# PowerSupply.net
KiCad netlist of a schematic drawn in Altium Designer
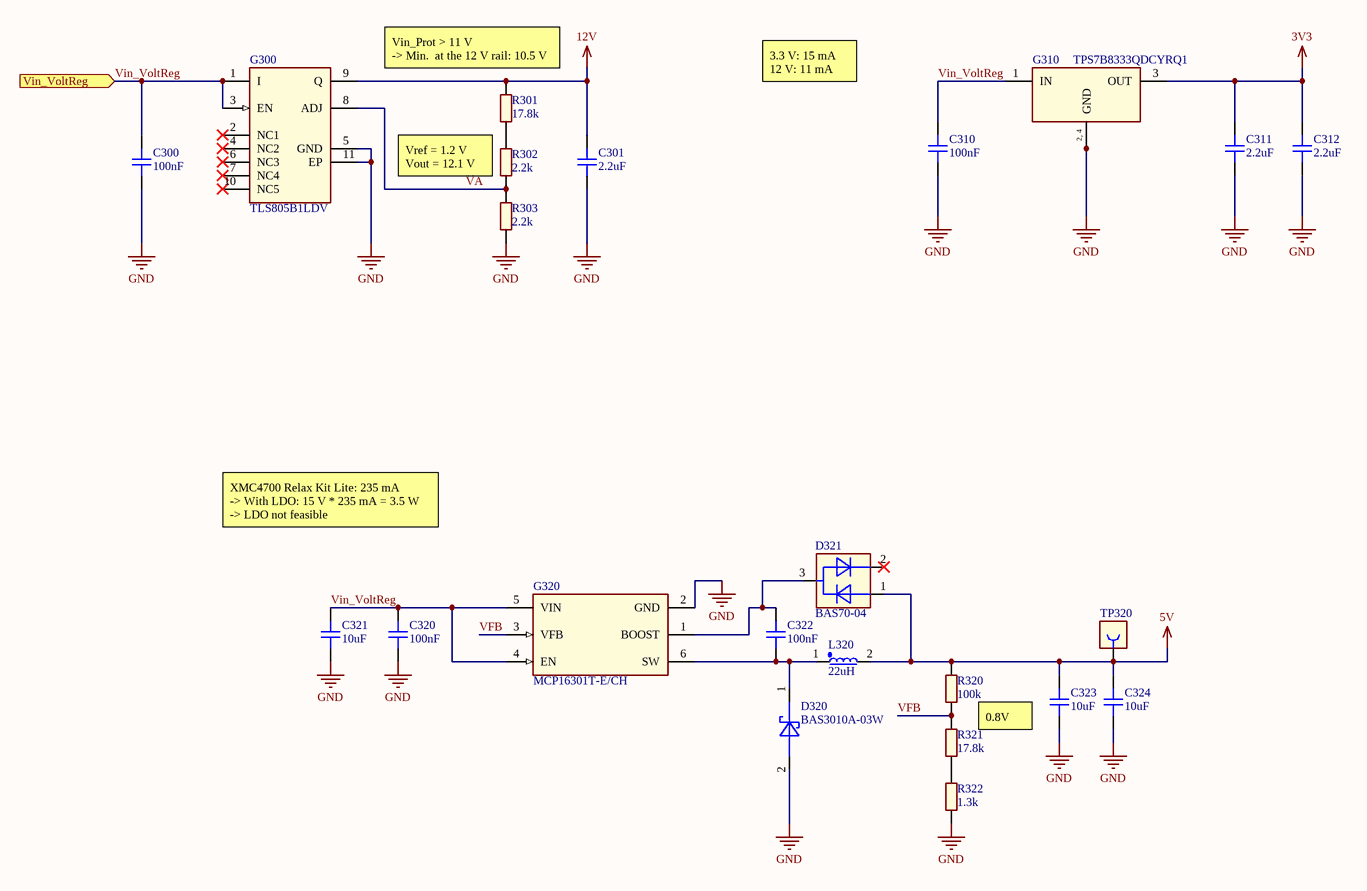
[diagram p0: PowerSupply.SchDoc]

(export (version "E")
  (design (tool "Eeschema 10.0.6"))
  (components
    (comp (ref "C300")
      (value "100nF")
      (footprint "CAPC1608X90N-2")
      (description "CAP / CERA / 100nF / 50V / 10% / X7R (EIA) / -55°C to 125°C / 0603 / SMD / -")
      (fields (field (name "MANUFACTURER") "AVX"))
      (libsource (lib "PCBLibraryData") (part "CAP-SGL-STD-02P_00000001"))
    )
    (comp (ref "C301")
      (value "2.2uF")
      (footprint "CAPC1608X90N-3")
      (description "CAP / CERA / 2.2uF / 25V / 10% / X5R (EIA) / -55°C to 85°C / 0603(1608) / SMD / -")
      (fields (field (name "LEGACY PARTNUMBER") "CAP01010924") (field (name "MANUFACTURER") "MuRata"))
      (libsource (lib "PCBLibraryData") (part "CAP-SGL-STD-02P_00000001"))
    )
    (comp (ref "C310")
      (value "100nF")
      (footprint "CAPC1608X90N-2")
      (description "CAP / CERA / 100nF / 50V / 10% / X7R (EIA) / -55°C to 125°C / 0603 / SMD / -")
      (fields (field (name "MANUFACTURER") "AVX"))
      (libsource (lib "PCBLibraryData") (part "CAP-SGL-STD-02P_00000001"))
    )
    (comp (ref "C311")
      (value "2.2uF")
      (footprint "CAPC1608X90N-3")
      (description "CAP / CERA / 2.2uF / 25V / 10% / X5R (EIA) / -55°C to 85°C / 0603(1608) / SMD / -")
      (fields (field (name "LEGACY PARTNUMBER") "CAP01010924") (field (name "MANUFACTURER") "MuRata"))
      (libsource (lib "PCBLibraryData") (part "CAP-SGL-STD-02P_00000001"))
    )
    (comp (ref "C312")
      (value "2.2uF")
      (footprint "CAPC1608X90N-3")
      (description "CAP / CERA / 2.2uF / 25V / 10% / X5R (EIA) / -55°C to 85°C / 0603(1608) / SMD / -")
      (fields (field (name "LEGACY PARTNUMBER") "CAP01010924") (field (name "MANUFACTURER") "MuRata"))
      (libsource (lib "PCBLibraryData") (part "CAP-SGL-STD-02P_00000001"))
    )
    (comp (ref "C320")
      (value "100nF")
      (footprint "CAPC1608X90N-2")
      (description "CAP / CERA / 100nF / 50V / 10% / X7R (EIA) / -55°C to 125°C / 0603 / SMD / -")
      (fields (field (name "MANUFACTURER") "AVX"))
      (libsource (lib "PCBLibraryData") (part "CAP-SGL-STD-02P_00000001"))
    )
    (comp (ref "C321")
      (value "10uF")
      (footprint "CAPC3216X190N-1")
      (description "CAP / CERA / 10uF / 50V / 20% / X5R (EIA) / -55°C to 85°C / 1206 (3216) / SMD / -")
      (fields (field (name "MANUFACTURER") "Taiyo Yuden"))
      (libsource (lib "PCBLibraryData") (part "CAP-SGL-STD-02P_00000001"))
    )
    (comp (ref "C322")
      (value "100nF")
      (footprint "CAPC1608X90N-2")
      (description "CAP / CERA / 100nF / 50V / 10% / X7R (EIA) / -55°C to 125°C / 0603 / SMD / -")
      (fields (field (name "MANUFACTURER") "AVX"))
      (libsource (lib "PCBLibraryData") (part "CAP-SGL-STD-02P_00000001"))
    )
    (comp (ref "C323")
      (value "10uF")
      (footprint "CAPC3216X190N-1")
      (description "CAP / CERA / 10uF / 50V / 20% / X5R (EIA) / -55°C to 85°C / 1206 (3216) / SMD / -")
      (fields (field (name "MANUFACTURER") "Taiyo Yuden"))
      (libsource (lib "PCBLibraryData") (part "CAP-SGL-STD-02P_00000001"))
    )
    (comp (ref "C324")
      (value "10uF")
      (footprint "CAPC3216X190N-1")
      (description "CAP / CERA / 10uF / 50V / 20% / X5R (EIA) / -55°C to 85°C / 1206 (3216) / SMD / -")
      (fields (field (name "MANUFACTURER") "Taiyo Yuden"))
      (libsource (lib "PCBLibraryData") (part "CAP-SGL-STD-02P_00000001"))
    )
    (comp (ref "D320")
      (value "BAS3010A-03W")
      (footprint "SOD2513X110N")
      (description "Medium Power AF Schottky Diode")
      (fields
        (field (name "LEGACY PARTNUMBER") "IFX01400145")
        (field (name "MANUFACTURER") "Infineon Technologies")
      )
      (libsource (lib "PCBLibraryData") (part "d_schottky_a"))
    )
    (comp (ref "D321")
      (value "BAS70-04")
      (footprint "SOT95P240X110-3N-1")
      (description "Silicon Schottky Diode")
      (fields
        (field (name "LEGACY PARTNUMBER") "IFX01400573")
        (field (name "MANUFACTURER") "Infineon Technologies")
      )
      (libsource (lib "PCBLibraryData") (part "d_dual_a1c2ac3_3p"))
    )
    (comp (ref "G300")
      (value "TLS805B1LDV")
      (footprint "SON50P330X330X110-11N-V")
      (description "Ultra Low Quiescent Current Linear Voltage Regulator, 5µA, Adjustable Output")
      (fields
        (field (name "LEGACY PARTNUMBER") "IFX01401037")
        (field (name "MANUFACTURER") "Infineon Technologies")
      )
      (libsource (lib "PCBLibraryData") (part "TLS805B1LDV"))
    )
    (comp (ref "G310")
      (value "TPS7B8333QDCYRQ1")
      (footprint "SOT230P700X180-4N")
      (description "Low-Dropout Regulator")
      (fields (field (name "MANUFACTURER") "Texas Instruments"))
      (libsource (lib "PCBLibraryData") (part "TL1963A-XXDCYX"))
    )
    (comp (ref "G320")
      (value "MCP16301T-E/CH")
      (footprint "SOT95P280X145-6N-9")
      (description "High-Voltage Input Integrated Switch Step-Down Regulator")
      (fields (field (name "MANUFACTURER") "Microchip Technology"))
      (libsource (lib "PCBLibraryData") (part "MCP16301"))
    )
    (comp (ref "L320")
      (value "22uH")
      (footprint "IND-SMD-74404064220")
      (fields (field (name "MANUFACTURER") "Wurth Elektronik"))
      (libsource (lib "PCBLibraryData") (part "IND-SGL-STD-WDG-COR-02P_0000002B"))
    )
    (comp (ref "R301")
      (value "17.8k")
      (footprint "RESC1609X50N")
      (description "RES / STD / 17.8k / 100mW / 1% / 100ppm/K / -55°C to 155°C / 0603 / SMD / -")
      (fields (field (name "LEGACY PARTNUMBER") "RES01801283") (field (name "MANUFACTURER") "Vishay"))
      (libsource (lib "PCBLibraryData") (part "RES-SGL-STD-02P_00000006"))
    )
    (comp (ref "R302")
      (value "2.2k")
      (footprint "RESC1609X50N")
      (description "RES / STD / 2.2k / 100mW / 1% / 100ppm/K / -55°C to 155°C / 0603 / SMD / -")
      (fields (field (name "LEGACY PARTNUMBER") "RES01801179") (field (name "MANUFACTURER") "Vishay"))
      (libsource (lib "PCBLibraryData") (part "RES-SGL-STD-02P_00000006"))
    )
    (comp (ref "R303")
      (value "2.2k")
      (footprint "RESC1609X50N")
      (description "RES / STD / 2.2k / 100mW / 1% / 100ppm/K / -55°C to 155°C / 0603 / SMD / -")
      (fields (field (name "LEGACY PARTNUMBER") "RES01801179") (field (name "MANUFACTURER") "Vishay"))
      (libsource (lib "PCBLibraryData") (part "RES-SGL-STD-02P_00000006"))
    )
    (comp (ref "R320")
      (value "100k")
      (footprint "RESC1609X50N")
      (description "RES / STD / 100k / 100mW / 1% / 100ppm/K / -55°C to 155°C / 0603 / SMD / -")
      (fields (field (name "LEGACY PARTNUMBER") "RES01801371") (field (name "MANUFACTURER") "Vishay"))
      (libsource (lib "") (part "RES-SGL-STD-02P_00000006_1"))
    )
    (comp (ref "R321")
      (value "17.8k")
      (footprint "RESC1609X50N")
      (description "RES / STD / 17.8k / 100mW / 1% / 100ppm/K / -55°C to 155°C / 0603 / SMD / -")
      (fields (field (name "LEGACY PARTNUMBER") "RES01801283") (field (name "MANUFACTURER") "Vishay"))
      (libsource (lib "PCBLibraryData") (part "RES-SGL-STD-02P_00000006"))
    )
    (comp (ref "R322")
      (value "1.3k")
      (footprint "RESC1609X50N")
      (description "RES / STD / 1.3k / 100mW / 1% / 100ppm/K / -55°C to 155°C / 0603 / SMD / -")
      (fields (field (name "LEGACY PARTNUMBER") "RES01801155") (field (name "MANUFACTURER") "Vishay"))
      (libsource (lib "PCBLibraryData") (part "RES-SGL-STD-02P_00000006"))
    )
    (comp (ref "TP320")
      (value "S1751-46R")
      (footprint "CON-SMD-TT-S1751-46")
      (description "Test Terminal, Surface Mount (Tape and Reeled Components)")
      (fields (field (name "LEGACY PARTNUMBER") "CON01501015") (field (name "MANUFACTURER") "Harwin"))
      (libsource (lib "PCBLibraryData") (part "connector_1_f"))
    )
  )
  (nets
    (net (code "1") (name "/VA") (class "Default")
      (node (ref "G300") (pin "8") (pinfunction "ADJ_8") (pintype "power_in"))
      (node (ref "R302") (pin "1") (pinfunction "1_1") (pintype "passive"))
      (node (ref "R303") (pin "2") (pinfunction "2_2") (pintype "passive"))
    )
    (net (code "2") (name "/VFB") (class "Default")
      (node (ref "G320") (pin "3") (pinfunction "VFB_3") (pintype "input"))
      (node (ref "R320") (pin "2") (pinfunction "2_2") (pintype "passive"))
      (node (ref "R321") (pin "2") (pinfunction "2_2") (pintype "passive"))
    )
    (net (code "3") (name "/Vin_VoltReg") (class "Default")
      (node (ref "C300") (pin "2") (pinfunction "2_2") (pintype "passive"))
      (node (ref "C310") (pin "2") (pinfunction "2_2") (pintype "passive"))
      (node (ref "C320") (pin "2") (pinfunction "2_2") (pintype "passive"))
      (node (ref "C321") (pin "2") (pinfunction "2_2") (pintype "passive"))
      (node (ref "G300") (pin "1") (pinfunction "I_1") (pintype "power_in"))
      (node (ref "G300") (pin "3") (pinfunction "EN_3") (pintype "input"))
      (node (ref "G310") (pin "1") (pinfunction "IN_1") (pintype "power_in"))
      (node (ref "G320") (pin "4") (pinfunction "EN_4") (pintype "input"))
      (node (ref "G320") (pin "5") (pinfunction "VIN_5") (pintype "power_in"))
    )
    (net (code "4") (name "3V3") (class "Default")
      (node (ref "C311") (pin "2") (pinfunction "2_2") (pintype "passive"))
      (node (ref "C312") (pin "2") (pinfunction "2_2") (pintype "passive"))
      (node (ref "G310") (pin "3") (pinfunction "OUT_3") (pintype "power_in"))
    )
    (net (code "5") (name "5V") (class "Default")
      (node (ref "C323") (pin "2") (pinfunction "2_2") (pintype "passive"))
      (node (ref "C324") (pin "2") (pinfunction "2_2") (pintype "passive"))
      (node (ref "D321") (pin "1") (pinfunction "ANODE_1") (pintype "passive"))
      (node (ref "L320") (pin "2") (pinfunction "2_2") (pintype "passive"))
      (node (ref "R320") (pin "1") (pinfunction "1_1") (pintype "passive"))
      (node (ref "TP320") (pin "1") (pinfunction "1_1") (pintype "passive"))
    )
    (net (code "6") (name "12V") (class "Default")
      (node (ref "C301") (pin "2") (pinfunction "2_2") (pintype "passive"))
      (node (ref "G300") (pin "9") (pinfunction "Q_9") (pintype "power_in"))
      (node (ref "R301") (pin "2") (pinfunction "2_2") (pintype "passive"))
    )
    (net (code "7") (name "GND") (class "Default")
      (node (ref "C300") (pin "1") (pinfunction "1_1") (pintype "passive"))
      (node (ref "C301") (pin "1") (pinfunction "1_1") (pintype "passive"))
      (node (ref "C310") (pin "1") (pinfunction "1_1") (pintype "passive"))
      (node (ref "C311") (pin "1") (pinfunction "1_1") (pintype "passive"))
      (node (ref "C312") (pin "1") (pinfunction "1_1") (pintype "passive"))
      (node (ref "C320") (pin "1") (pinfunction "1_1") (pintype "passive"))
      (node (ref "C321") (pin "1") (pinfunction "1_1") (pintype "passive"))
      (node (ref "C323") (pin "1") (pinfunction "1_1") (pintype "passive"))
      (node (ref "C324") (pin "1") (pinfunction "1_1") (pintype "passive"))
      (node (ref "D320") (pin "2") (pinfunction "Anode_2") (pintype "passive"))
      (node (ref "G300") (pin "11") (pinfunction "EP_11") (pintype "power_in"))
      (node (ref "G300") (pin "5") (pinfunction "GND_5") (pintype "power_in"))
      (node (ref "G310") (pin "2") (pinfunction "GND_2") (pintype "power_in"))
      (node (ref "G310") (pin "4") (pinfunction "GND_4") (pintype "power_in"))
      (node (ref "G320") (pin "2") (pinfunction "GND_2") (pintype "power_in"))
      (node (ref "R303") (pin "1") (pinfunction "1_1") (pintype "passive"))
      (node (ref "R322") (pin "1") (pinfunction "1_1") (pintype "passive"))
    )
    (net (code "8") (name "Net-(D320-Cathode)") (class "Default")
      (node (ref "C322") (pin "1") (pinfunction "1_1") (pintype "passive"))
      (node (ref "D320") (pin "1") (pinfunction "Cathode_1") (pintype "passive"))
      (node (ref "G320") (pin "6") (pinfunction "SW_6") (pintype "passive"))
      (node (ref "L320") (pin "1") (pinfunction "1_1") (pintype "passive"))
    )
    (net (code "9") (name "Net-(D321-ANODE_{slash}_CATHODE)") (class "Default")
      (node (ref "C322") (pin "2") (pinfunction "2_2") (pintype "passive"))
      (node (ref "D321") (pin "3") (pinfunction "ANODE_/_CATHODE_3") (pintype "passive"))
      (node (ref "G320") (pin "1") (pinfunction "BOOST_1") (pintype "power_in"))
    )
    (net (code "10") (name "Net-(R301-Pad1)") (class "Default")
      (node (ref "R301") (pin "1") (pinfunction "1_1") (pintype "passive"))
      (node (ref "R302") (pin "2") (pinfunction "2_2") (pintype "passive"))
    )
    (net (code "11") (name "Net-(R321-Pad1)") (class "Default")
      (node (ref "R321") (pin "1") (pinfunction "1_1") (pintype "passive"))
      (node (ref "R322") (pin "2") (pinfunction "2_2") (pintype "passive"))
    )
    (net (code "12") (name "unconnected-(D321-CATHODE-Pad2)") (class "Default")
      (node (ref "D321") (pin "2") (pinfunction "CATHODE_2") (pintype "passive+no_connect"))
    )
    (net (code "13") (name "unconnected-(G300-NC1-Pad2)") (class "Default")
      (node (ref "G300") (pin "2") (pinfunction "NC1_2") (pintype "passive+no_connect"))
    )
    (net (code "14") (name "unconnected-(G300-NC2-Pad4)") (class "Default")
      (node (ref "G300") (pin "4") (pinfunction "NC2_4") (pintype "passive+no_connect"))
    )
    (net (code "15") (name "unconnected-(G300-NC3-Pad6)") (class "Default")
      (node (ref "G300") (pin "6") (pinfunction "NC3_6") (pintype "passive+no_connect"))
    )
    (net (code "16") (name "unconnected-(G300-NC4-Pad7)") (class "Default")
      (node (ref "G300") (pin "7") (pinfunction "NC4_7") (pintype "passive+no_connect"))
    )
    (net (code "17") (name "unconnected-(G300-NC5-Pad10)") (class "Default")
      (node (ref "G300") (pin "10") (pinfunction "NC5_10") (pintype "passive+no_connect"))
    )
  )
)
